# Mico_SDCard_SPI.net
KiCad netlist of a schematic drawn in Altium Designer
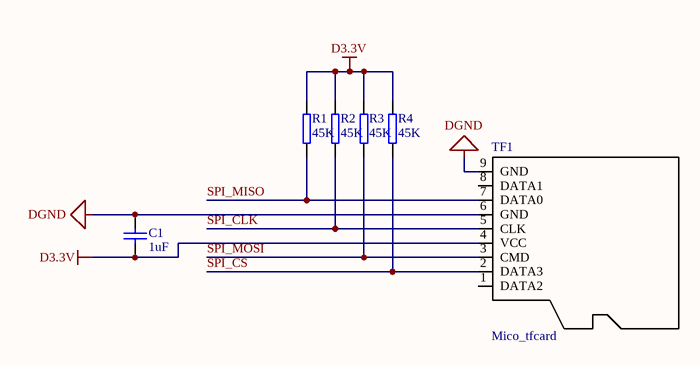
[diagram p0: Mico_SDCard_SPI.SchDoc]

(export (version "E")
  (design (tool "Eeschema 10.0.6"))
  (components
    (comp (ref "C1")
      (value "1uF")
      (footprint "0603C")
      (description "贴片电容")
      (libsource (lib "常用元件") (part "Cap"))
    )
    (comp (ref "R1") (value "45K") (footprint "2512R") (libsource (lib "常用元件") (part "RES-10K")))
    (comp (ref "R2") (value "45K") (footprint "0402R") (libsource (lib "常用元件") (part "RES-10K")))
    (comp (ref "R3") (value "45K") (footprint "0402R") (libsource (lib "常用元件") (part "RES-10K")))
    (comp (ref "R4") (value "45K") (footprint "0402R") (libsource (lib "常用元件") (part "RES-10K")))
    (comp (ref "TF1")
      (value "Mico_tfcard")
      (footprint "Micro_SDCard")
      (libsource (lib "常用元件") (part "Mico_tfcard"))
    )
  )
  (nets
    (net (code "1") (name "/SPI_CLK") (class "Default")
      (node (ref "R2") (pin "1") (pinfunction "1_1") (pintype "passive"))
      (node (ref "TF1") (pin "5") (pinfunction "CLK_5") (pintype "passive"))
    )
    (net (code "2") (name "/SPI_CS") (class "Default")
      (node (ref "R4") (pin "1") (pinfunction "1_1") (pintype "passive"))
      (node (ref "TF1") (pin "2") (pinfunction "DATA3_2") (pintype "passive"))
    )
    (net (code "3") (name "/SPI_MISO") (class "Default")
      (node (ref "R1") (pin "1") (pinfunction "1_1") (pintype "passive"))
      (node (ref "TF1") (pin "7") (pinfunction "DATA0_7") (pintype "passive"))
    )
    (net (code "4") (name "/SPI_MOSI") (class "Default")
      (node (ref "R3") (pin "1") (pinfunction "1_1") (pintype "passive"))
      (node (ref "TF1") (pin "3") (pinfunction "CMD_3") (pintype "passive"))
    )
    (net (code "5") (name "D3.3V") (class "Default")
      (node (ref "C1") (pin "1") (pinfunction "1_1") (pintype "passive"))
      (node (ref "R1") (pin "2") (pinfunction "2_2") (pintype "passive"))
      (node (ref "R2") (pin "2") (pinfunction "2_2") (pintype "passive"))
      (node (ref "R3") (pin "2") (pinfunction "2_2") (pintype "passive"))
      (node (ref "R4") (pin "2") (pinfunction "2_2") (pintype "passive"))
      (node (ref "TF1") (pin "4") (pinfunction "VCC_4") (pintype "passive"))
    )
    (net (code "6") (name "DGND") (class "Default")
      (node (ref "C1") (pin "2") (pinfunction "2_2") (pintype "passive"))
      (node (ref "TF1") (pin "6") (pinfunction "GND_6") (pintype "passive"))
      (node (ref "TF1") (pin "9") (pinfunction "GND_9") (pintype "passive"))
    )
    (net (code "7") (name "unconnected-(TF1-DATA1-Pad8)") (class "Default")
      (node (ref "TF1") (pin "8") (pinfunction "DATA1_8") (pintype "passive"))
    )
    (net (code "8") (name "unconnected-(TF1-DATA2-Pad1)") (class "Default")
      (node (ref "TF1") (pin "1") (pinfunction "DATA2_1") (pintype "passive"))
    )
  )
)
